# MIC_ATHIdeF.net
KiCad netlist of a schematic drawn in EAGLE
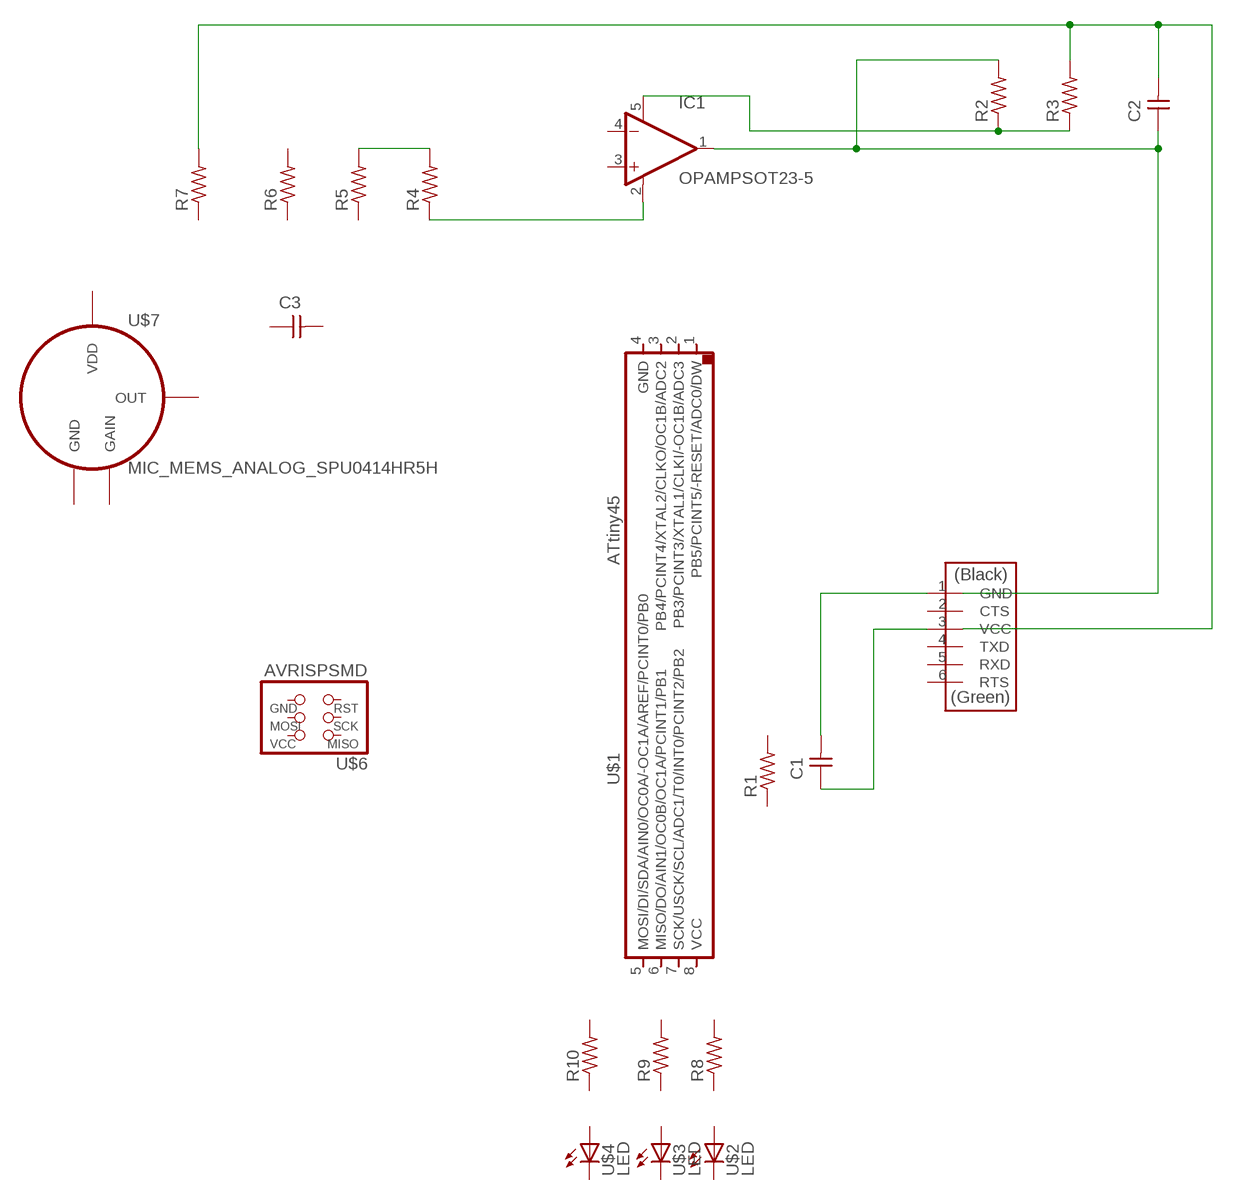
[diagram p0: schematic, sheet 1]

(export (version "E")
  (design (tool "Eeschema 10.0.6"))
  (components
    (comp (ref "C1")
      (value "CAP-UNPOLARIZED")
      (footprint "eagle-import:C1206")
      (libsource (lib "eagle-import") (part "CAP-UNPOLARIZED"))
    )
    (comp (ref "C2")
      (value "CAP-UNPOLARIZED")
      (footprint "eagle-import:C1206")
      (libsource (lib "eagle-import") (part "CAP-UNPOLARIZED"))
    )
    (comp (ref "C3")
      (value "CAP-UNPOLARIZED")
      (footprint "eagle-import:C1206")
      (libsource (lib "eagle-import") (part "CAP-UNPOLARIZED"))
    )
    (comp (ref "IC1")
      (value "OPAMPSOT23-5")
      (footprint "eagle-import:SOT23-5")
      (libsource (lib "eagle-import") (part "OPAMPSOT23-5"))
    )
    (comp (ref "R1")
      (value "RES-US1206")
      (footprint "eagle-import:R1206")
      (libsource (lib "eagle-import") (part "RES-US1206"))
    )
    (comp (ref "R2")
      (value "RES-US1206")
      (footprint "eagle-import:R1206")
      (libsource (lib "eagle-import") (part "RES-US1206"))
    )
    (comp (ref "R3")
      (value "RES-US1206")
      (footprint "eagle-import:R1206")
      (libsource (lib "eagle-import") (part "RES-US1206"))
    )
    (comp (ref "R4")
      (value "RES-US1206")
      (footprint "eagle-import:R1206")
      (libsource (lib "eagle-import") (part "RES-US1206"))
    )
    (comp (ref "R5")
      (value "RES-US1206")
      (footprint "eagle-import:R1206")
      (libsource (lib "eagle-import") (part "RES-US1206"))
    )
    (comp (ref "R6")
      (value "RES-US1206")
      (footprint "eagle-import:R1206")
      (libsource (lib "eagle-import") (part "RES-US1206"))
    )
    (comp (ref "R7")
      (value "RES-US1206")
      (footprint "eagle-import:R1206")
      (libsource (lib "eagle-import") (part "RES-US1206"))
    )
    (comp (ref "R8")
      (value "RES-US1206")
      (footprint "eagle-import:R1206")
      (libsource (lib "eagle-import") (part "RES-US1206"))
    )
    (comp (ref "R9")
      (value "RES-US1206")
      (footprint "eagle-import:R1206")
      (libsource (lib "eagle-import") (part "RES-US1206"))
    )
    (comp (ref "R10")
      (value "RES-US1206")
      (footprint "eagle-import:R1206")
      (libsource (lib "eagle-import") (part "RES-US1206"))
    )
    (comp (ref "U$1")
      (value "ATTINY45SI")
      (footprint "eagle-import:SOIC8")
      (libsource (lib "eagle-import") (part "ATTINY45SI"))
    )
    (comp (ref "U$2")
      (value "LED")
      (footprint "eagle-import:LED1206")
      (libsource (lib "eagle-import") (part "LED"))
    )
    (comp (ref "U$3")
      (value "LED")
      (footprint "eagle-import:LED1206")
      (libsource (lib "eagle-import") (part "LED"))
    )
    (comp (ref "U$4")
      (value "LED")
      (footprint "eagle-import:LED1206")
      (libsource (lib "eagle-import") (part "LED"))
    )
    (comp (ref "U$5")
      (value "FTDI-SMD-HEADER")
      (footprint "eagle-import:1X06SMD")
      (libsource (lib "eagle-import") (part "FTDI-SMD-HEADER"))
    )
    (comp (ref "U$6")
      (value "AVRISPSMD")
      (footprint "eagle-import:2X03SMD")
      (libsource (lib "eagle-import") (part "AVRISPSMD"))
    )
    (comp (ref "U$7")
      (value "MIC_MEMS_ANALOG_SPU0414HR5H")
      (footprint "eagle-import:MIC_MEMS_ANALOG_SPU0414HR5H")
      (libsource (lib "eagle-import") (part "MIC_MEMS_ANALOG_SPU0414HR5H"))
    )
  )
  (nets
    (net (code "1") (name "/GND") (class "Default")
      (node (ref "U$7") (pin "2") (pinfunction "GND_2") (pintype "power_in"))
    )
    (net (code "2") (name "/VDD") (class "Default")
      (node (ref "U$7") (pin "1") (pinfunction "VDD_1") (pintype "power_in"))
    )
    (net (code "3") (name "Net-(C2-Pad2)") (class "Default")
      (node (ref "C2") (pin "2") (pinfunction "2_2") (pintype "passive"))
      (node (ref "R3") (pin "2") (pinfunction "2_2") (pintype "passive"))
      (node (ref "R7") (pin "2") (pinfunction "2_2") (pintype "passive"))
    )
    (net (code "4") (name "Net-(IC1-OUT)") (class "Default")
      (node (ref "C2") (pin "1") (pinfunction "1_1") (pintype "passive"))
      (node (ref "IC1") (pin "1") (pinfunction "OUT_1") (pintype "output"))
      (node (ref "R2") (pin "2") (pinfunction "2_2") (pintype "passive"))
    )
    (net (code "5") (name "Net-(IC1-V+)") (class "Default")
      (node (ref "IC1") (pin "5") (pinfunction "V+_5") (pintype "power_in"))
      (node (ref "R2") (pin "1") (pinfunction "1_1") (pintype "passive"))
      (node (ref "R3") (pin "1") (pinfunction "1_1") (pintype "passive"))
    )
    (net (code "6") (name "Net-(IC1-V-)") (class "Default")
      (node (ref "IC1") (pin "2") (pinfunction "V-_2") (pintype "power_in"))
      (node (ref "R4") (pin "1") (pinfunction "1_1") (pintype "passive"))
    )
    (net (code "7") (name "Net-(R4-Pad2)") (class "Default")
      (node (ref "R4") (pin "2") (pinfunction "2_2") (pintype "passive"))
      (node (ref "R5") (pin "2") (pinfunction "2_2") (pintype "passive"))
    )
    (net (code "8") (name "Net-(U$5-GND)") (class "Default")
      (node (ref "C1") (pin "2") (pinfunction "2_2") (pintype "passive"))
      (node (ref "U$5") (pin "1") (pinfunction "GND_1") (pintype "bidirectional"))
    )
    (net (code "9") (name "Net-(U$5-VCC)") (class "Default")
      (node (ref "C1") (pin "1") (pinfunction "1_1") (pintype "passive"))
      (node (ref "U$5") (pin "3") (pinfunction "VCC_3") (pintype "bidirectional"))
    )
    (net (code "10") (name "unconnected-(C3-Pad1)") (class "Default")
      (node (ref "C3") (pin "1") (pinfunction "1_1") (pintype "passive"))
    )
    (net (code "11") (name "unconnected-(C3-Pad2)") (class "Default")
      (node (ref "C3") (pin "2") (pinfunction "2_2") (pintype "passive"))
    )
    (net (code "12") (name "unconnected-(IC1-+IN-Pad3)") (class "Default")
      (node (ref "IC1") (pin "3") (pinfunction "+IN_3") (pintype "input"))
    )
    (net (code "13") (name "unconnected-(IC1--IN-Pad4)") (class "Default")
      (node (ref "IC1") (pin "4") (pinfunction "-IN_4") (pintype "input"))
    )
    (net (code "14") (name "unconnected-(R1-Pad1)") (class "Default")
      (node (ref "R1") (pin "1") (pinfunction "1_1") (pintype "passive"))
    )
    (net (code "15") (name "unconnected-(R1-Pad2)") (class "Default")
      (node (ref "R1") (pin "2") (pinfunction "2_2") (pintype "passive"))
    )
    (net (code "16") (name "unconnected-(R5-Pad1)") (class "Default")
      (node (ref "R5") (pin "1") (pinfunction "1_1") (pintype "passive"))
    )
    (net (code "17") (name "unconnected-(R6-Pad1)") (class "Default")
      (node (ref "R6") (pin "1") (pinfunction "1_1") (pintype "passive"))
    )
    (net (code "18") (name "unconnected-(R6-Pad2)") (class "Default")
      (node (ref "R6") (pin "2") (pinfunction "2_2") (pintype "passive"))
    )
    (net (code "19") (name "unconnected-(R7-Pad1)") (class "Default")
      (node (ref "R7") (pin "1") (pinfunction "1_1") (pintype "passive"))
    )
    (net (code "20") (name "unconnected-(R8-Pad1)") (class "Default")
      (node (ref "R8") (pin "1") (pinfunction "1_1") (pintype "passive"))
    )
    (net (code "21") (name "unconnected-(R8-Pad2)") (class "Default")
      (node (ref "R8") (pin "2") (pinfunction "2_2") (pintype "passive"))
    )
    (net (code "22") (name "unconnected-(R9-Pad1)") (class "Default")
      (node (ref "R9") (pin "1") (pinfunction "1_1") (pintype "passive"))
    )
    (net (code "23") (name "unconnected-(R9-Pad2)") (class "Default")
      (node (ref "R9") (pin "2") (pinfunction "2_2") (pintype "passive"))
    )
    (net (code "24") (name "unconnected-(R10-Pad1)") (class "Default")
      (node (ref "R10") (pin "1") (pinfunction "1_1") (pintype "passive"))
    )
    (net (code "25") (name "unconnected-(R10-Pad2)") (class "Default")
      (node (ref "R10") (pin "2") (pinfunction "2_2") (pintype "passive"))
    )
    (net (code "26") (name "unconnected-(U$1-GND-Pad4)") (class "Default")
      (node (ref "U$1") (pin "4") (pinfunction "GND_4") (pintype "bidirectional"))
    )
    (net (code "27") (name "unconnected-(U$1-MISO{slash}DO{slash}AIN1{slash}OC0B{slash}OC1A{slash}PCINT1{slash}PB1-Pad6)") (class "Default")
      (node (ref "U$1") (pin "6") (pinfunction "MISO/DO/AIN1/OC0B/OC1A/PCINT1/PB1_6") (pintype "bidirectional"))
    )
    (net (code "28") (name "unconnected-(U$1-MOSI{slash}DI{slash}SDA{slash}AIN0{slash}OC0A{slash}-OC1A{slash}AREF{slash}PCINT0{slash}PB0-Pad5)") (class "Default")
      (node (ref "U$1") (pin "5") (pinfunction "MOSI/DI/SDA/AIN0/OC0A/-OC1A/AREF/PCINT0/PB0_5") (pintype "bidirectional"))
    )
    (net (code "29") (name "unconnected-(U$1-PB3{slash}PCINT3{slash}XTAL1{slash}CLKI{slash}-OC1B{slash}ADC3-Pad2)") (class "Default")
      (node (ref "U$1") (pin "2") (pinfunction "PB3/PCINT3/XTAL1/CLKI/-OC1B/ADC3_2") (pintype "bidirectional"))
    )
    (net (code "30") (name "unconnected-(U$1-PB4{slash}PCINT4{slash}XTAL2{slash}CLKO{slash}OC1B{slash}ADC2-Pad3)") (class "Default")
      (node (ref "U$1") (pin "3") (pinfunction "PB4/PCINT4/XTAL2/CLKO/OC1B/ADC2_3") (pintype "bidirectional"))
    )
    (net (code "31") (name "unconnected-(U$1-PB5{slash}PCINT5{slash}-RESET{slash}ADC0{slash}DW-Pad1)") (class "Default")
      (node (ref "U$1") (pin "1") (pinfunction "PB5/PCINT5/-RESET/ADC0/DW_1") (pintype "bidirectional"))
    )
    (net (code "32") (name "unconnected-(U$1-SCK{slash}USCK{slash}SCL{slash}ADC1{slash}T0{slash}INT0{slash}PCINT2{slash}PB2-Pad7)") (class "Default")
      (node (ref "U$1") (pin "7") (pinfunction "SCK/USCK/SCL/ADC1/T0/INT0/PCINT2/PB2_7") (pintype "bidirectional"))
    )
    (net (code "33") (name "unconnected-(U$1-VCC-Pad8)") (class "Default")
      (node (ref "U$1") (pin "8") (pinfunction "VCC_8") (pintype "bidirectional"))
    )
    (net (code "34") (name "unconnected-(U$2-A-Pad1)") (class "Default")
      (node (ref "U$2") (pin "1") (pinfunction "A_1") (pintype "passive"))
    )
    (net (code "35") (name "unconnected-(U$2-C-Pad2)") (class "Default")
      (node (ref "U$2") (pin "2") (pinfunction "C_2") (pintype "passive"))
    )
    (net (code "36") (name "unconnected-(U$3-A-Pad1)") (class "Default")
      (node (ref "U$3") (pin "1") (pinfunction "A_1") (pintype "passive"))
    )
    (net (code "37") (name "unconnected-(U$3-C-Pad2)") (class "Default")
      (node (ref "U$3") (pin "2") (pinfunction "C_2") (pintype "passive"))
    )
    (net (code "38") (name "unconnected-(U$4-A-Pad1)") (class "Default")
      (node (ref "U$4") (pin "1") (pinfunction "A_1") (pintype "passive"))
    )
    (net (code "39") (name "unconnected-(U$4-C-Pad2)") (class "Default")
      (node (ref "U$4") (pin "2") (pinfunction "C_2") (pintype "passive"))
    )
    (net (code "40") (name "unconnected-(U$5-CTS-Pad2)") (class "Default")
      (node (ref "U$5") (pin "2") (pinfunction "CTS_2") (pintype "bidirectional"))
    )
    (net (code "41") (name "unconnected-(U$5-RTS-Pad6)") (class "Default")
      (node (ref "U$5") (pin "6") (pinfunction "RTS_6") (pintype "bidirectional"))
    )
    (net (code "42") (name "unconnected-(U$5-RXD-Pad5)") (class "Default")
      (node (ref "U$5") (pin "5") (pinfunction "RXD_5") (pintype "bidirectional"))
    )
    (net (code "43") (name "unconnected-(U$5-TXD-Pad4)") (class "Default")
      (node (ref "U$5") (pin "4") (pinfunction "TXD_4") (pintype "bidirectional"))
    )
    (net (code "44") (name "unconnected-(U$6-GND-Pad6)") (class "Default")
      (node (ref "U$6") (pin "6") (pinfunction "GND_6") (pintype "passive"))
    )
    (net (code "45") (name "unconnected-(U$6-MISO-Pad1)") (class "Default")
      (node (ref "U$6") (pin "1") (pinfunction "MISO_1") (pintype "passive"))
    )
    (net (code "46") (name "unconnected-(U$6-MOSI-Pad4)") (class "Default")
      (node (ref "U$6") (pin "4") (pinfunction "MOSI_4") (pintype "passive"))
    )
    (net (code "47") (name "unconnected-(U$6-RST-Pad5)") (class "Default")
      (node (ref "U$6") (pin "5") (pinfunction "RST_5") (pintype "passive"))
    )
    (net (code "48") (name "unconnected-(U$6-SCK-Pad3)") (class "Default")
      (node (ref "U$6") (pin "3") (pinfunction "SCK_3") (pintype "passive"))
    )
    (net (code "49") (name "unconnected-(U$6-VCC-Pad2)") (class "Default")
      (node (ref "U$6") (pin "2") (pinfunction "VCC_2") (pintype "passive"))
    )
    (net (code "50") (name "unconnected-(U$7-GAIN-Pad3)") (class "Default")
      (node (ref "U$7") (pin "3") (pinfunction "GAIN_3") (pintype "bidirectional"))
    )
    (net (code "51") (name "unconnected-(U$7-OUT-Pad4)") (class "Default")
      (node (ref "U$7") (pin "4") (pinfunction "OUT_4") (pintype "output"))
    )
  )
)
